# design.net
KiCad netlist of a schematic drawn in Altium Designer
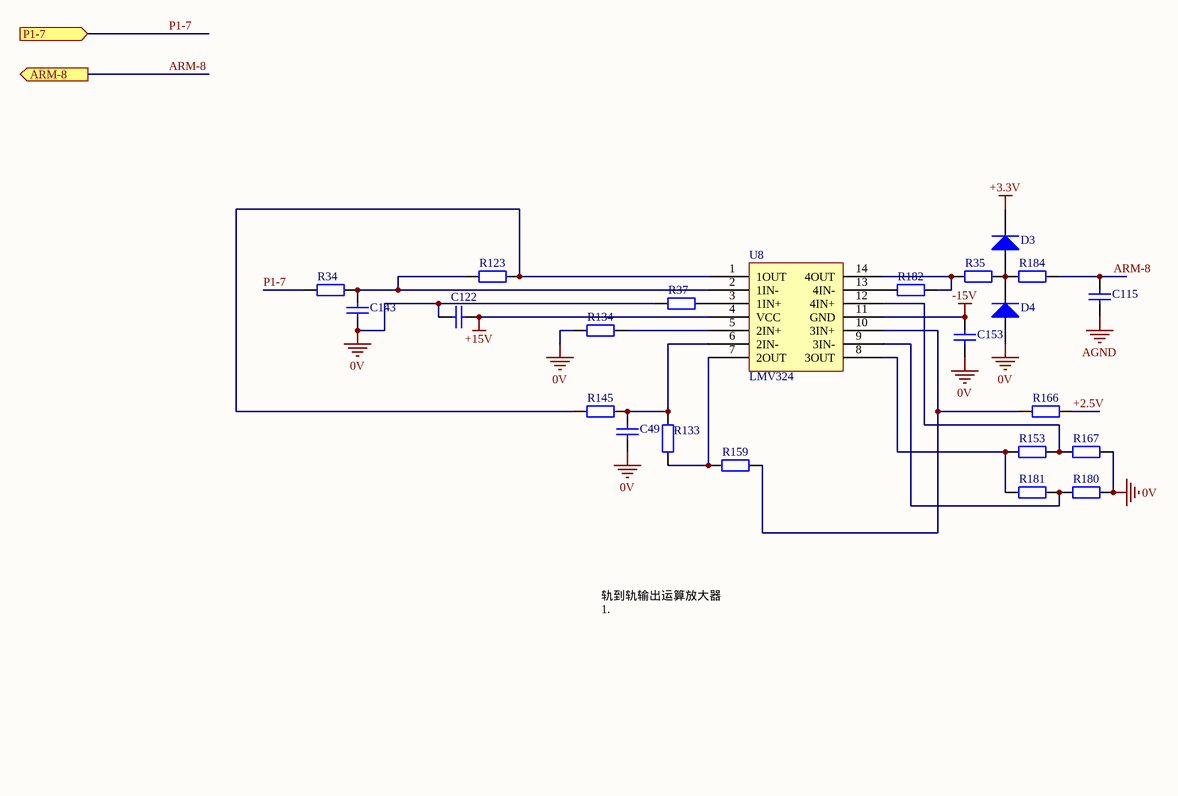
[diagram p0: 四通道输出运算放大.SchDoc]

(export (version "E")
  (design (tool "Eeschema 10.0.6"))
  (components
    (comp (ref "C49")
      (value "Cap")
      (footprint "RAD-0.3")
      (description "Capacitor")
      (fields (field (name "PUBLISHER") "Altium Limited"))
      (libsource (lib "Miscellaneous Devices") (part "Cap"))
    )
    (comp (ref "C115")
      (value "Cap")
      (footprint "RAD-0.3")
      (description "Capacitor")
      (fields (field (name "PUBLISHER") "Altium Limited"))
      (libsource (lib "Miscellaneous Devices") (part "Cap"))
    )
    (comp (ref "C122")
      (value "Cap")
      (footprint "RAD-0.3")
      (description "Capacitor")
      (fields (field (name "PUBLISHER") "Altium Limited"))
      (libsource (lib "Miscellaneous Devices") (part "Cap"))
    )
    (comp (ref "C143")
      (value "Cap")
      (footprint "RAD-0.3")
      (description "Capacitor")
      (fields (field (name "PUBLISHER") "Altium Limited"))
      (libsource (lib "Miscellaneous Devices") (part "Cap"))
    )
    (comp (ref "C153")
      (value "Cap")
      (footprint "RAD-0.3")
      (description "Capacitor")
      (fields (field (name "PUBLISHER") "Altium Limited"))
      (libsource (lib "Miscellaneous Devices") (part "Cap"))
    )
    (comp (ref "D3")
      (value "Diode 1N4007")
      (footprint "DO-41")
      (description "1 Amp General Purpose Rectifier")
      (fields (field (name "PUBLISHER") "Altium Limited"))
      (libsource (lib "Miscellaneous Devices") (part "Diode 1N4007"))
    )
    (comp (ref "D4")
      (value "Diode 1N4007")
      (footprint "DO-41")
      (description "1 Amp General Purpose Rectifier")
      (fields (field (name "PUBLISHER") "Altium Limited"))
      (libsource (lib "Miscellaneous Devices") (part "Diode 1N4007"))
    )
    (comp (ref "R34")
      (value "Res2")
      (footprint "AXIAL-0.4")
      (description "Resistor")
      (fields (field (name "PUBLISHER") "Altium Limited"))
      (libsource (lib "") (part "Res2_1"))
    )
    (comp (ref "R35")
      (value "Res2")
      (footprint "AXIAL-0.4")
      (description "Resistor")
      (fields (field (name "PUBLISHER") "Altium Limited"))
      (libsource (lib "Miscellaneous Devices") (part "Res2"))
    )
    (comp (ref "R37")
      (value "Res2")
      (footprint "AXIAL-0.4")
      (description "Resistor")
      (fields (field (name "PUBLISHER") "Altium Limited"))
      (libsource (lib "") (part "Res2_1"))
    )
    (comp (ref "R123")
      (value "Res2")
      (footprint "AXIAL-0.4")
      (description "Resistor")
      (fields (field (name "PUBLISHER") "Altium Limited"))
      (libsource (lib "") (part "Res2_1"))
    )
    (comp (ref "R133")
      (value "Res2")
      (footprint "AXIAL-0.4")
      (description "Resistor")
      (fields (field (name "PUBLISHER") "Altium Limited"))
      (libsource (lib "") (part "Res2_2"))
    )
    (comp (ref "R134")
      (value "Res2")
      (footprint "AXIAL-0.4")
      (description "Resistor")
      (fields (field (name "PUBLISHER") "Altium Limited"))
      (libsource (lib "") (part "Res2_1"))
    )
    (comp (ref "R145")
      (value "Res2")
      (footprint "AXIAL-0.4")
      (description "Resistor")
      (fields (field (name "PUBLISHER") "Altium Limited"))
      (libsource (lib "") (part "Res2_1"))
    )
    (comp (ref "R153")
      (value "Res2")
      (footprint "AXIAL-0.4")
      (description "Resistor")
      (fields (field (name "PUBLISHER") "Altium Limited"))
      (libsource (lib "Miscellaneous Devices") (part "Res2"))
    )
    (comp (ref "R159")
      (value "Res2")
      (footprint "AXIAL-0.4")
      (description "Resistor")
      (fields (field (name "PUBLISHER") "Altium Limited"))
      (libsource (lib "Miscellaneous Devices") (part "Res2"))
    )
    (comp (ref "R166")
      (value "Res2")
      (footprint "AXIAL-0.4")
      (description "Resistor")
      (fields (field (name "PUBLISHER") "Altium Limited"))
      (libsource (lib "Miscellaneous Devices") (part "Res2"))
    )
    (comp (ref "R167")
      (value "Res2")
      (footprint "AXIAL-0.4")
      (description "Resistor")
      (fields (field (name "PUBLISHER") "Altium Limited"))
      (libsource (lib "Miscellaneous Devices") (part "Res2"))
    )
    (comp (ref "R180")
      (value "Res2")
      (footprint "AXIAL-0.4")
      (description "Resistor")
      (fields (field (name "PUBLISHER") "Altium Limited"))
      (libsource (lib "Miscellaneous Devices") (part "Res2"))
    )
    (comp (ref "R181")
      (value "Res2")
      (footprint "AXIAL-0.4")
      (description "Resistor")
      (fields (field (name "PUBLISHER") "Altium Limited"))
      (libsource (lib "Miscellaneous Devices") (part "Res2"))
    )
    (comp (ref "R182")
      (value "Res2")
      (footprint "AXIAL-0.4")
      (description "Resistor")
      (fields (field (name "PUBLISHER") "Altium Limited"))
      (libsource (lib "Miscellaneous Devices") (part "Res2"))
    )
    (comp (ref "R184")
      (value "Res2")
      (footprint "AXIAL-0.4")
      (description "Resistor")
      (fields (field (name "PUBLISHER") "Altium Limited"))
      (libsource (lib "Miscellaneous Devices") (part "Res2"))
    )
    (comp (ref "U8") (value "LMV324") (libsource (lib "LMV324") (part "Component_1")))
  )
  (nets
    (net (code "1") (name "+3.3V") (class "Default")
      (node (ref "D3") (pin "2") (pinfunction "K_2") (pintype "passive"))
    )
    (net (code "2") (name "+15V") (class "Default")
      (node (ref "C122") (pin "1") (pinfunction "1_1") (pintype "passive"))
      (node (ref "U8") (pin "4") (pinfunction "VCC_4") (pintype "passive"))
    )
    (net (code "3") (name "-15V") (class "Default")
      (node (ref "C153") (pin "2") (pinfunction "2_2") (pintype "passive"))
      (node (ref "U8") (pin "11") (pinfunction "GND_11") (pintype "passive"))
    )
    (net (code "4") (name "/+2.5V") (class "Default")
      (node (ref "R166") (pin "2") (pinfunction "2_2") (pintype "passive"))
    )
    (net (code "5") (name "/ARM-8") (class "Default")
      (node (ref "C115") (pin "2") (pinfunction "2_2") (pintype "passive"))
      (node (ref "R184") (pin "2") (pinfunction "2_2") (pintype "passive"))
    )
    (net (code "6") (name "/P1-7") (class "Default")
      (node (ref "R34") (pin "2") (pinfunction "2_2") (pintype "passive"))
    )
    (net (code "7") (name "0V") (class "Default")
      (node (ref "C122") (pin "2") (pinfunction "2_2") (pintype "passive"))
      (node (ref "C143") (pin "1") (pinfunction "1_1") (pintype "passive"))
      (node (ref "C153") (pin "1") (pinfunction "1_1") (pintype "passive"))
      (node (ref "C49") (pin "1") (pinfunction "1_1") (pintype "passive"))
      (node (ref "D4") (pin "1") (pinfunction "A_1") (pintype "passive"))
      (node (ref "R134") (pin "2") (pinfunction "2_2") (pintype "passive"))
      (node (ref "R167") (pin "2") (pinfunction "2_2") (pintype "passive"))
      (node (ref "R180") (pin "2") (pinfunction "2_2") (pintype "passive"))
      (node (ref "R37") (pin "2") (pinfunction "2_2") (pintype "passive"))
    )
    (net (code "8") (name "AGND") (class "Default")
      (node (ref "C115") (pin "1") (pinfunction "1_1") (pintype "passive"))
    )
    (net (code "9") (name "Net-(D3-A)") (class "Default")
      (node (ref "D3") (pin "1") (pinfunction "A_1") (pintype "passive"))
      (node (ref "D4") (pin "2") (pinfunction "K_2") (pintype "passive"))
      (node (ref "R184") (pin "1") (pinfunction "1_1") (pintype "passive"))
      (node (ref "R35") (pin "2") (pinfunction "2_2") (pintype "passive"))
    )
    (net (code "10") (name "Net-(U8-1IN+)") (class "Default")
      (node (ref "R37") (pin "1") (pinfunction "1_1") (pintype "passive"))
      (node (ref "U8") (pin "3") (pinfunction "1IN+_3") (pintype "passive"))
    )
    (net (code "11") (name "Net-(U8-1IN-)") (class "Default")
      (node (ref "C143") (pin "2") (pinfunction "2_2") (pintype "passive"))
      (node (ref "R123") (pin "2") (pinfunction "2_2") (pintype "passive"))
      (node (ref "R34") (pin "1") (pinfunction "1_1") (pintype "passive"))
      (node (ref "U8") (pin "2") (pinfunction "1IN-_2") (pintype "passive"))
    )
    (net (code "12") (name "Net-(U8-1OUT)") (class "Default")
      (node (ref "R123") (pin "1") (pinfunction "1_1") (pintype "passive"))
      (node (ref "R145") (pin "2") (pinfunction "2_2") (pintype "passive"))
      (node (ref "U8") (pin "1") (pinfunction "1OUT_1") (pintype "passive"))
    )
    (net (code "13") (name "Net-(U8-2IN+)") (class "Default")
      (node (ref "R134") (pin "1") (pinfunction "1_1") (pintype "passive"))
      (node (ref "U8") (pin "5") (pinfunction "2IN+_5") (pintype "passive"))
    )
    (net (code "14") (name "Net-(U8-2IN-)") (class "Default")
      (node (ref "C49") (pin "2") (pinfunction "2_2") (pintype "passive"))
      (node (ref "R133") (pin "2") (pinfunction "2_2") (pintype "passive"))
      (node (ref "R145") (pin "1") (pinfunction "1_1") (pintype "passive"))
      (node (ref "U8") (pin "6") (pinfunction "2IN-_6") (pintype "passive"))
    )
    (net (code "15") (name "Net-(U8-2OUT)") (class "Default")
      (node (ref "R133") (pin "1") (pinfunction "1_1") (pintype "passive"))
      (node (ref "R159") (pin "1") (pinfunction "1_1") (pintype "passive"))
      (node (ref "U8") (pin "7") (pinfunction "2OUT_7") (pintype "passive"))
    )
    (net (code "16") (name "Net-(U8-3IN+)") (class "Default")
      (node (ref "R159") (pin "2") (pinfunction "2_2") (pintype "passive"))
      (node (ref "R166") (pin "1") (pinfunction "1_1") (pintype "passive"))
      (node (ref "U8") (pin "10") (pinfunction "3IN+_10") (pintype "passive"))
    )
    (net (code "17") (name "Net-(U8-3IN-)") (class "Default")
      (node (ref "R180") (pin "1") (pinfunction "1_1") (pintype "passive"))
      (node (ref "R181") (pin "2") (pinfunction "2_2") (pintype "passive"))
      (node (ref "U8") (pin "9") (pinfunction "3IN-_9") (pintype "passive"))
    )
    (net (code "18") (name "Net-(U8-3OUT)") (class "Default")
      (node (ref "R153") (pin "1") (pinfunction "1_1") (pintype "passive"))
      (node (ref "R181") (pin "1") (pinfunction "1_1") (pintype "passive"))
      (node (ref "U8") (pin "8") (pinfunction "3OUT_8") (pintype "passive"))
    )
    (net (code "19") (name "Net-(U8-4IN+)") (class "Default")
      (node (ref "R153") (pin "2") (pinfunction "2_2") (pintype "passive"))
      (node (ref "R167") (pin "1") (pinfunction "1_1") (pintype "passive"))
      (node (ref "U8") (pin "12") (pinfunction "4IN+_12") (pintype "passive"))
    )
    (net (code "20") (name "Net-(U8-4IN-)") (class "Default")
      (node (ref "R182") (pin "1") (pinfunction "1_1") (pintype "passive"))
      (node (ref "U8") (pin "13") (pinfunction "4IN-_13") (pintype "passive"))
    )
    (net (code "21") (name "Net-(U8-4OUT)") (class "Default")
      (node (ref "R182") (pin "2") (pinfunction "2_2") (pintype "passive"))
      (node (ref "R35") (pin "1") (pinfunction "1_1") (pintype "passive"))
      (node (ref "U8") (pin "14") (pinfunction "4OUT_14") (pintype "passive"))
    )
  )
)
